# sd_card.net
KiCad netlist of a schematic drawn in Altium Designer
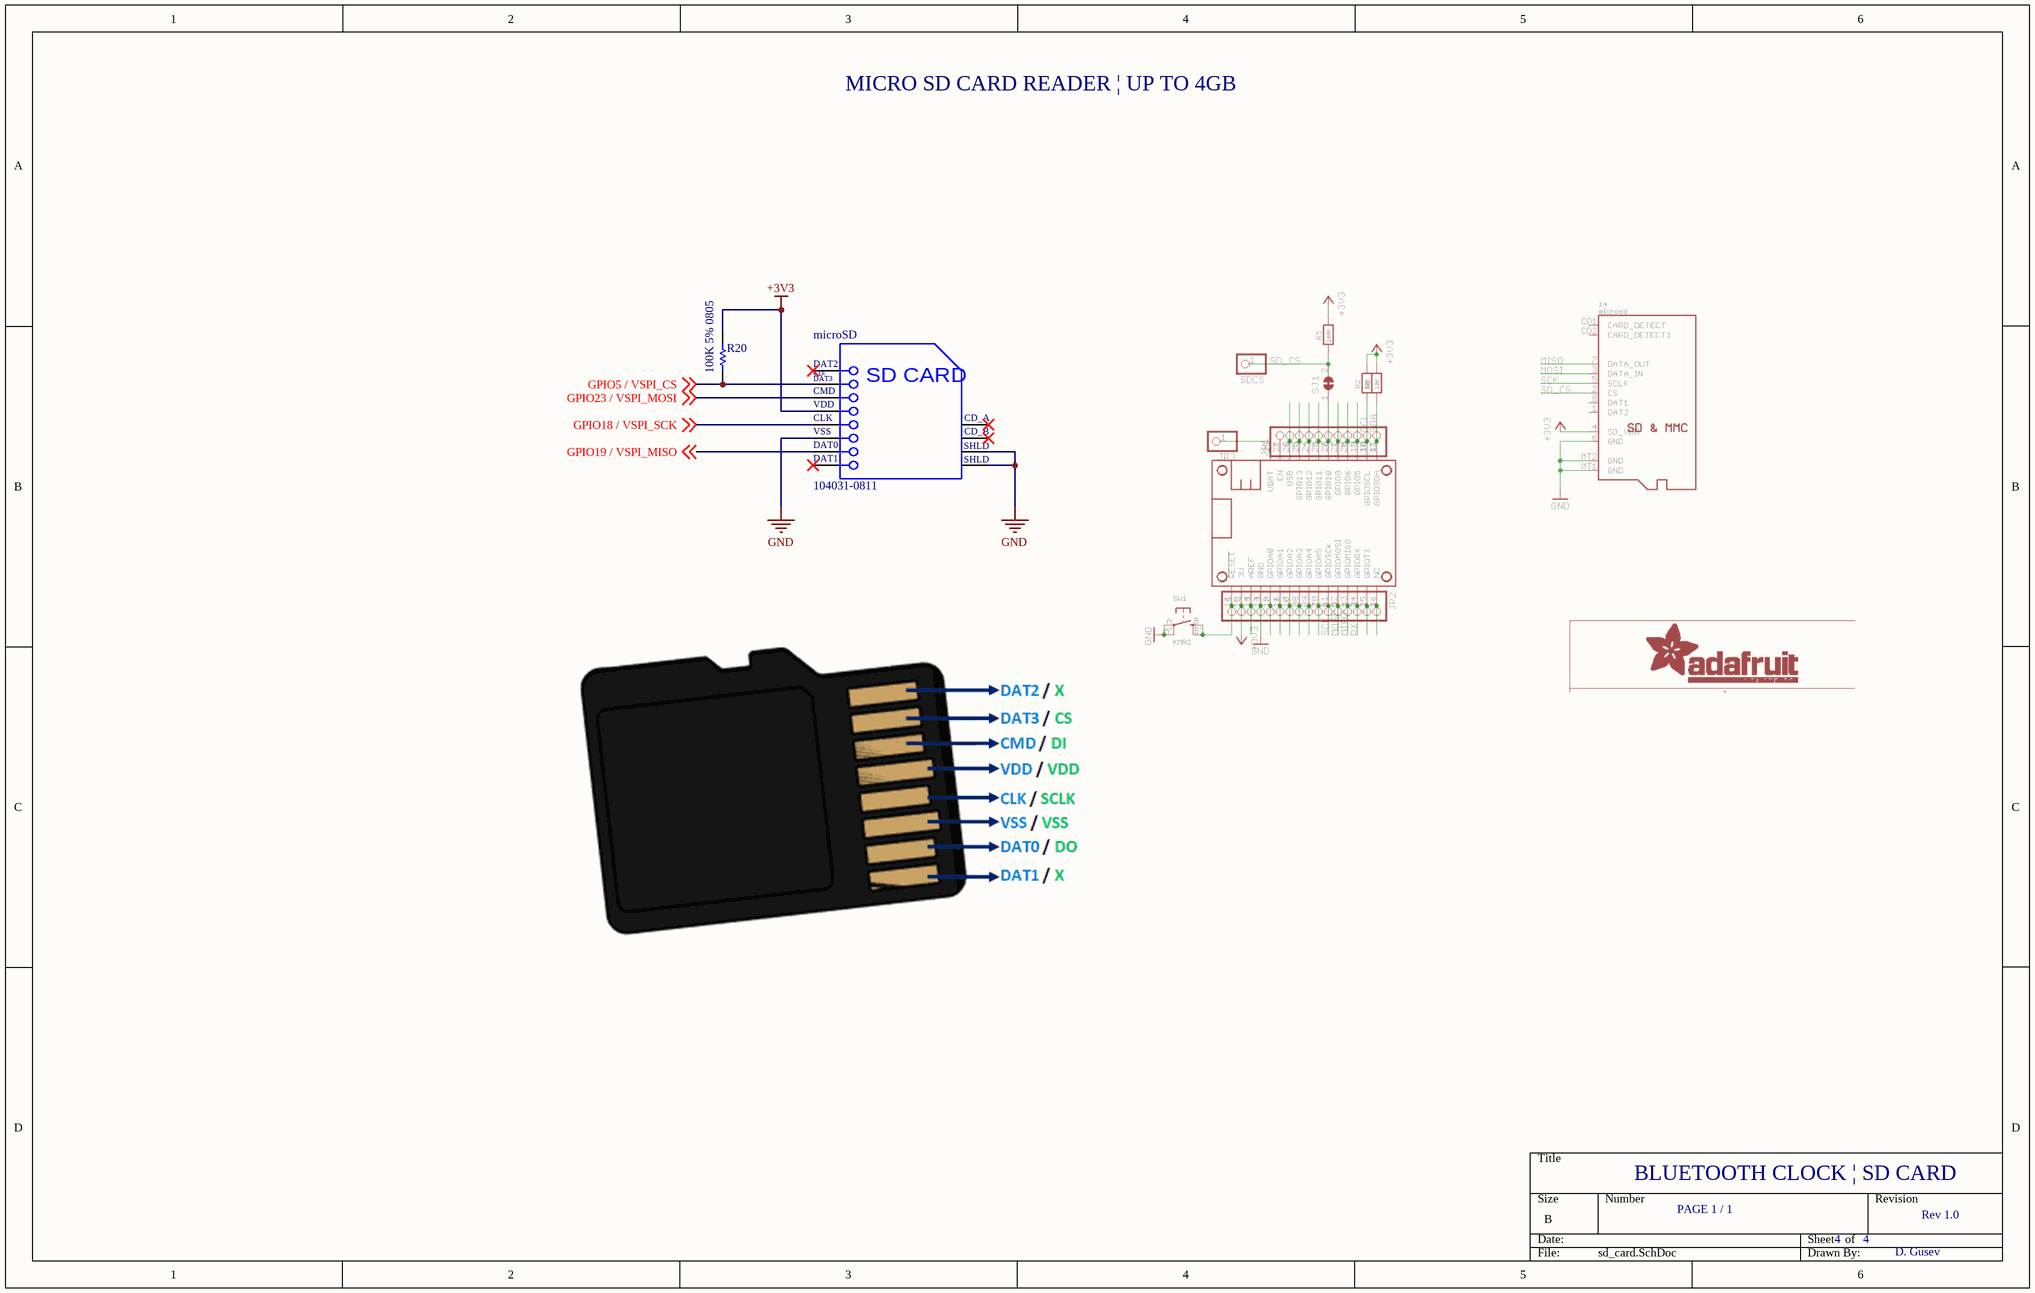
[diagram p0: sd_card.SchDoc]

(export (version "E")
  (design (tool "Eeschema 10.0.6"))
  (components
    (comp (ref "microSD")
      (value "104031-0811")
      (footprint "MOLX-104031-0811_V")
      (description "Micro SD Card, RA, -25 to 85 degC, 8-Pin SMD, RoHS, Tape and Reel")
      (fields (field (name "MANUFACTURER") "Molex"))
      (libsource (lib "Altium Content Vault") (part "CN-SD-8-2SW-2S"))
    )
    (comp (ref "R20")
      (value "100K 5% 0805")
      (footprint "RESC2013X70X40ML20T20")
      (fields (field (name "PART NUMBER") "ERJ-6ENF1003V") (field (name "MANUFACTURER") "Panasonic"))
      (libsource (lib "Altium Content Vault") (part "RES"))
    )
  )
  (nets
    (net (code "1") (name "+3V3") (class "Default")
      (node (ref "R20") (pin "2") (pinfunction "2_2") (pintype "passive"))
      (node (ref "microSD") (pin "4") (pinfunction "VDD_4") (pintype "passive"))
    )
    (net (code "2") (name "GND") (class "Default")
      (node (ref "microSD") (pin "11") (pinfunction "SHLD1_11") (pintype "passive"))
      (node (ref "microSD") (pin "12") (pinfunction "SHLD2_12") (pintype "passive"))
      (node (ref "microSD") (pin "6") (pinfunction "VSS2_6") (pintype "passive"))
    )
    (net (code "3") (name "GPIO5 {slash} VSPI_CS") (class "Default")
      (node (ref "R20") (pin "1") (pinfunction "1_1") (pintype "passive"))
      (node (ref "microSD") (pin "2") (pinfunction "CMD_2") (pintype "passive"))
    )
    (net (code "4") (name "GPIO18 {slash} VSPI_SCK") (class "Default")
      (node (ref "microSD") (pin "5") (pinfunction "CLK_5") (pintype "passive"))
    )
    (net (code "5") (name "GPIO19 {slash} VSPI_MISO") (class "Default")
      (node (ref "microSD") (pin "7") (pinfunction "DAT0_7") (pintype "passive"))
    )
    (net (code "6") (name "GPIO23 {slash} VSPI_MOSI") (class "Default")
      (node (ref "microSD") (pin "3") (pinfunction "VSS1_3") (pintype "passive"))
    )
    (net (code "7") (name "unconnected-(microSD-CD_A-Pad9)") (class "Default")
      (node (ref "microSD") (pin "9") (pinfunction "CD_A_9") (pintype "passive+no_connect"))
    )
    (net (code "8") (name "unconnected-(microSD-CD_B-Pad10)") (class "Default")
      (node (ref "microSD") (pin "10") (pinfunction "CD_B_10") (pintype "passive+no_connect"))
    )
    (net (code "9") (name "unconnected-(microSD-CD{slash}DAT3-Pad1)") (class "Default")
      (node (ref "microSD") (pin "1") (pinfunction "CD/DAT3_1") (pintype "passive+no_connect"))
    )
    (net (code "10") (name "unconnected-(microSD-DAT1-Pad8)") (class "Default")
      (node (ref "microSD") (pin "8") (pinfunction "DAT1_8") (pintype "passive+no_connect"))
    )
  )
)
